# xdoftof_revA.net
KiCad netlist of a schematic drawn in EAGLE
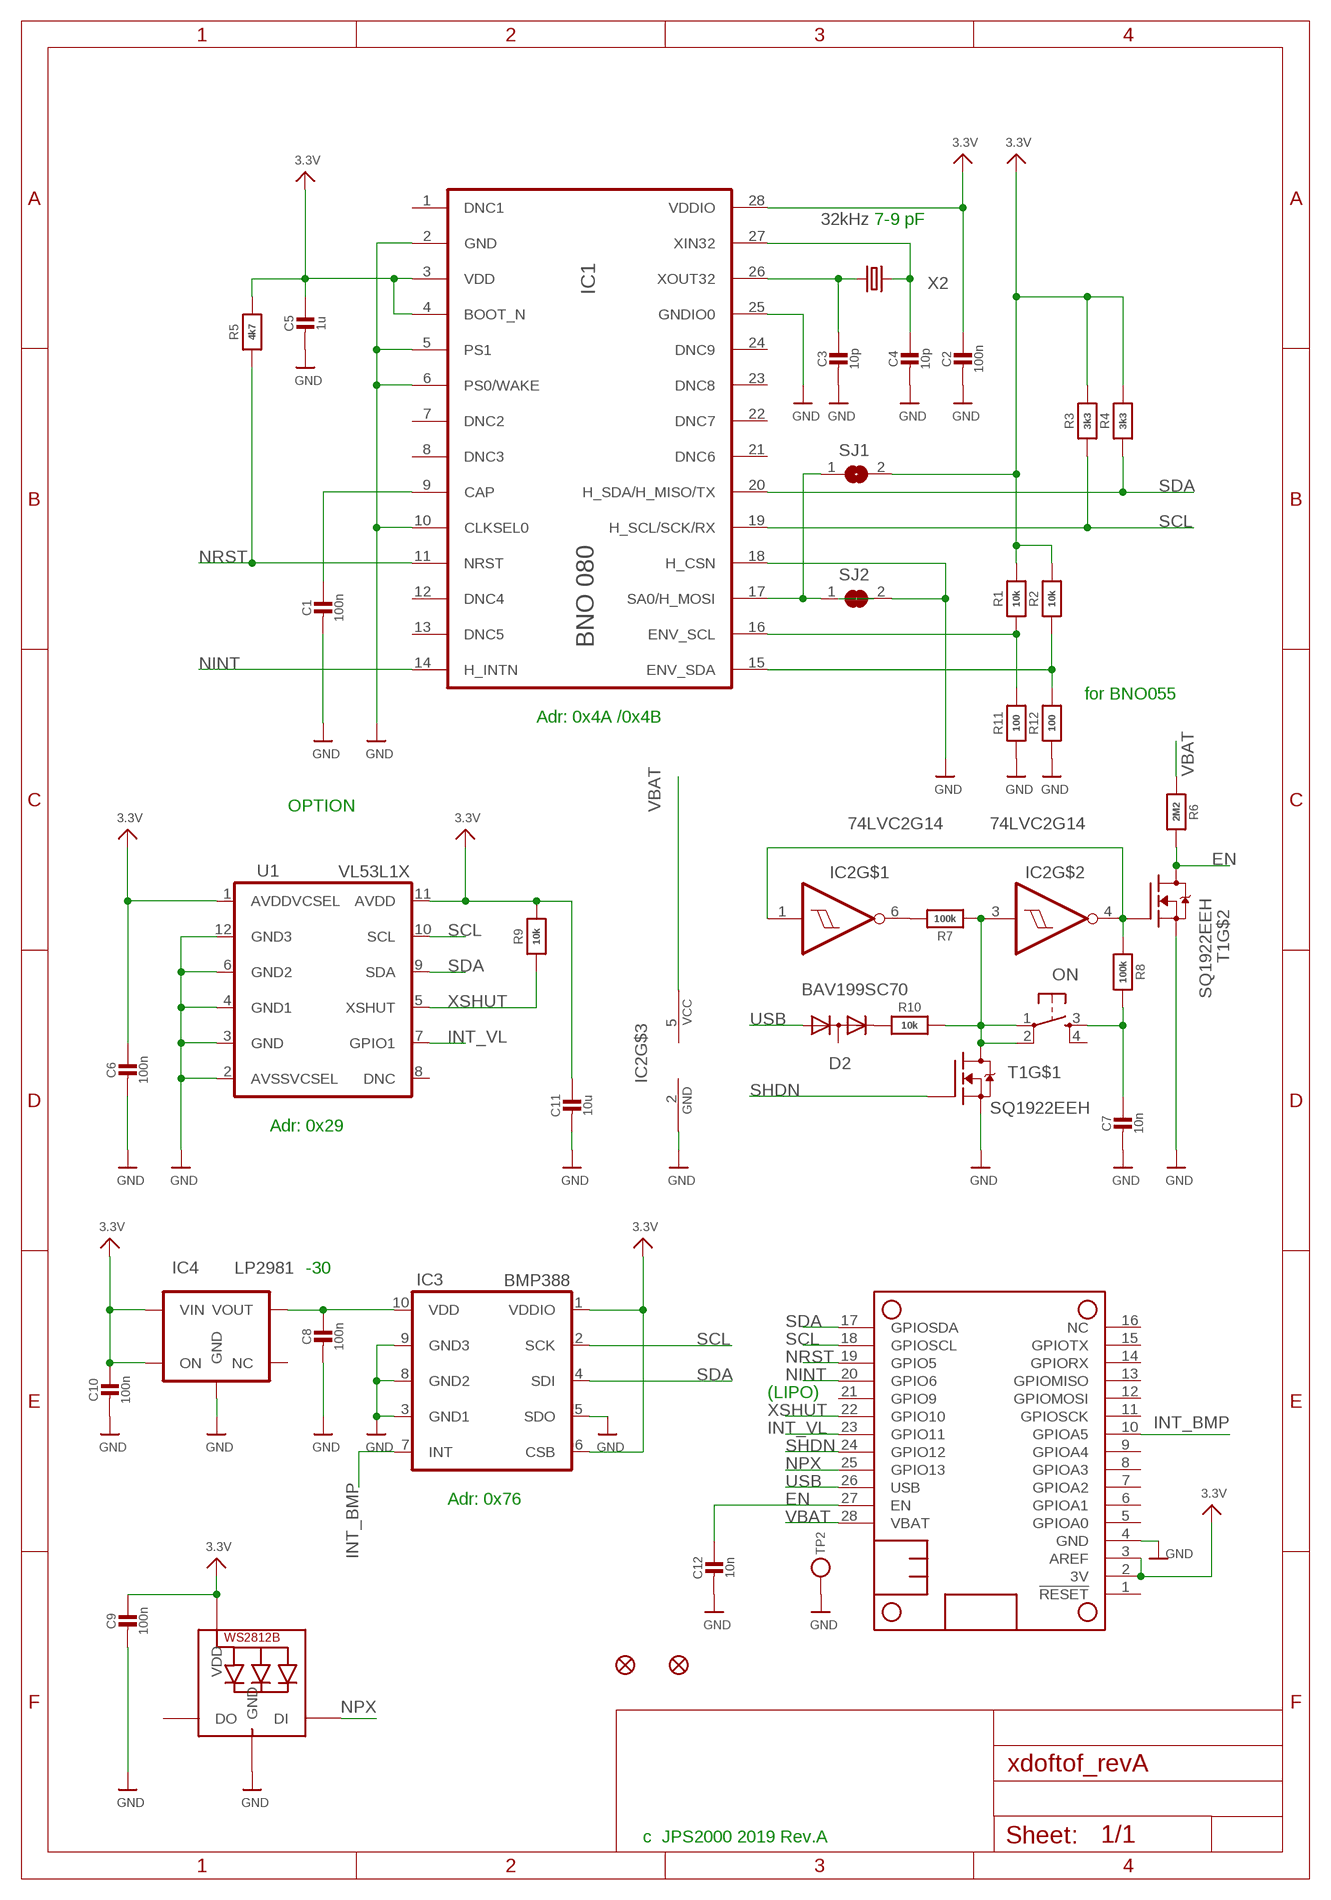
[diagram p0: schematic, sheet 1]

(export (version "E")
  (design (tool "Eeschema 10.0.6"))
  (components
    (comp (ref "C1")
      (value "100n")
      (footprint "eagle-import:0603-NO")
      (libsource (lib "eagle-import") (part "CAP_CERAMIC0603_NO"))
    )
    (comp (ref "C2")
      (value "100n")
      (footprint "eagle-import:0603-NO")
      (libsource (lib "eagle-import") (part "CAP_CERAMIC0603_NO"))
    )
    (comp (ref "C3")
      (value "10p")
      (footprint "eagle-import:0603-NO")
      (libsource (lib "eagle-import") (part "CAP_CERAMIC0603_NO"))
    )
    (comp (ref "C4")
      (value "10p")
      (footprint "eagle-import:0603-NO")
      (libsource (lib "eagle-import") (part "CAP_CERAMIC0603_NO"))
    )
    (comp (ref "C5")
      (value "1u")
      (footprint "eagle-import:0603-NO")
      (libsource (lib "eagle-import") (part "CAP_CERAMIC0603_NO"))
    )
    (comp (ref "C6")
      (value "100n")
      (footprint "eagle-import:0603-NO")
      (libsource (lib "eagle-import") (part "CAP_CERAMIC0603_NO"))
    )
    (comp (ref "C7")
      (value "10n")
      (footprint "eagle-import:0603-NO")
      (libsource (lib "eagle-import") (part "CAP_CERAMIC0603_NO"))
    )
    (comp (ref "C8")
      (value "100n")
      (footprint "eagle-import:0603-NO")
      (libsource (lib "eagle-import") (part "CAP_CERAMIC0603_NO"))
    )
    (comp (ref "C9")
      (value "100n")
      (footprint "eagle-import:0603-NO")
      (libsource (lib "eagle-import") (part "CAP_CERAMIC0603_NO"))
    )
    (comp (ref "C10")
      (value "100n")
      (footprint "eagle-import:0603-NO")
      (libsource (lib "eagle-import") (part "CAP_CERAMIC0603_NO"))
    )
    (comp (ref "C11")
      (value "10u")
      (footprint "eagle-import:0603-NO")
      (libsource (lib "eagle-import") (part "CAP_CERAMIC0603_NO"))
    )
    (comp (ref "C12")
      (value "10n")
      (footprint "eagle-import:0603-NO")
      (libsource (lib "eagle-import") (part "CAP_CERAMIC0603_NO"))
    )
    (comp (ref "D2")
      (value "BAV199SC70")
      (footprint "eagle-import:SC70")
      (libsource (lib "eagle-import") (part "BAV199SC70"))
    )
    (comp (ref "FID1")
      (value "FIDUCIAL\"\"")
      (footprint "eagle-import:FIDUCIAL_1MM")
      (libsource (lib "eagle-import") (part "FIDUCIAL{dblquote}{dblquote}"))
    )
    (comp (ref "FID2")
      (value "FIDUCIAL\"\"")
      (footprint "eagle-import:FIDUCIAL_1MM")
      (libsource (lib "eagle-import") (part "FIDUCIAL{dblquote}{dblquote}"))
    )
    (comp (ref "IC1")
      (value "BNO080")
      (footprint "eagle-import:LGA28")
      (libsource (lib "eagle-import") (part "BNO080"))
    )
    (comp (ref "IC2")
      (value "74LVC2G14")
      (footprint "eagle-import:SC70-6")
      (libsource (lib "eagle-import") (part "74LVC2G14"))
    )
    (comp (ref "IC3")
      (value "BMP388")
      (footprint "eagle-import:LGA10")
      (libsource (lib "eagle-import") (part "BMP388"))
    )
    (comp (ref "IC4")
      (value "LP2981")
      (footprint "eagle-import:SOT23-5_NEW")
      (libsource (lib "eagle-import") (part "LP2981"))
    )
    (comp (ref "LED1")
      (value "WS2812B3535")
      (footprint "eagle-import:LED3535")
      (libsource (lib "eagle-import") (part "WS2812B3535"))
    )
    (comp (ref "MS1")
      (value "FEATHERWING_NOHOLES")
      (footprint "eagle-import:FEATHERWING_NOHOLES")
      (libsource (lib "eagle-import") (part "FEATHERWING_NOHOLES"))
    )
    (comp (ref "ON")
      (value "ON/OFF")
      (footprint "eagle-import:TACTSWSKQGABE010")
      (libsource (lib "eagle-import") (part "TACTSW_SMD"))
    )
    (comp (ref "R1")
      (value "10k")
      (footprint "eagle-import:_0603MP")
      (libsource (lib "eagle-import") (part "RESISTOR_0603MP"))
    )
    (comp (ref "R2")
      (value "10k")
      (footprint "eagle-import:_0603MP")
      (libsource (lib "eagle-import") (part "RESISTOR_0603MP"))
    )
    (comp (ref "R3")
      (value "3k3")
      (footprint "eagle-import:_0603MP")
      (libsource (lib "eagle-import") (part "RESISTOR_0603MP"))
    )
    (comp (ref "R4")
      (value "3k3")
      (footprint "eagle-import:_0603MP")
      (libsource (lib "eagle-import") (part "RESISTOR_0603MP"))
    )
    (comp (ref "R5")
      (value "4k7")
      (footprint "eagle-import:_0603MP")
      (libsource (lib "eagle-import") (part "RESISTOR_0603MP"))
    )
    (comp (ref "R6")
      (value "2M2")
      (footprint "eagle-import:_0603MP")
      (libsource (lib "eagle-import") (part "RESISTOR_0603MP"))
    )
    (comp (ref "R7")
      (value "100k")
      (footprint "eagle-import:_0603MP")
      (libsource (lib "eagle-import") (part "RESISTOR_0603MP"))
    )
    (comp (ref "R8")
      (value "100k")
      (footprint "eagle-import:_0603MP")
      (libsource (lib "eagle-import") (part "RESISTOR_0603MP"))
    )
    (comp (ref "R9")
      (value "10k")
      (footprint "eagle-import:_0603MP")
      (libsource (lib "eagle-import") (part "RESISTOR_0603MP"))
    )
    (comp (ref "R10")
      (value "10k")
      (footprint "eagle-import:_0603MP")
      (libsource (lib "eagle-import") (part "RESISTOR_0603MP"))
    )
    (comp (ref "R11")
      (value "100")
      (footprint "eagle-import:_0603MP")
      (libsource (lib "eagle-import") (part "RESISTOR_0603MP"))
    )
    (comp (ref "R12")
      (value "100")
      (footprint "eagle-import:_0603MP")
      (libsource (lib "eagle-import") (part "RESISTOR_0603MP"))
    )
    (comp (ref "SJ1")
      (value "SOLDERJUMPERREFLOW_NOPASTE")
      (footprint "eagle-import:SOLDERJUMPER_REFLOW_NOPASTE")
      (libsource (lib "eagle-import") (part "SOLDERJUMPERREFLOW_NOPASTE"))
    )
    (comp (ref "SJ2")
      (value "SOLDERJUMPERCLOSED")
      (footprint "eagle-import:SOLDERJUMPER_CLOSEDWIRE")
      (libsource (lib "eagle-import") (part "SOLDERJUMPERCLOSED"))
    )
    (comp (ref "T1")
      (value "SQ1922EEH")
      (footprint "eagle-import:SC70-6")
      (libsource (lib "eagle-import") (part "DUAL_NMOS"))
    )
    (comp (ref "TP2")
      (value "TESTPOINTROUND1MM")
      (footprint "eagle-import:TESTPOINT_ROUND_1MM")
      (libsource (lib "eagle-import") (part "TESTPOINTROUND1MM"))
    )
    (comp (ref "U1")
      (value "VL53L1X")
      (footprint "eagle-import:VL53L1X")
      (libsource (lib "eagle-import") (part "VL53L1X"))
    )
    (comp (ref "X2")
      (value "32kHz")
      (footprint "eagle-import:XTAL_SMD1")
      (libsource (lib "eagle-import") (part "XTAL_SMD"))
    )
  )
  (nets
    (net (code "1") (name "/EN") (class "Default")
      (node (ref "C12") (pin "1") (pinfunction "1_1") (pintype "passive"))
      (node (ref "MS1") (pin "27") (pinfunction "EN_27") (pintype "passive"))
      (node (ref "R6") (pin "2") (pinfunction "2_2") (pintype "passive"))
      (node (ref "T1") (pin "3") (pinfunction "D_3") (pintype "passive"))
    )
    (net (code "2") (name "/INT_BMP") (class "Default")
      (node (ref "IC3") (pin "7") (pinfunction "INT_7") (pintype "output"))
      (node (ref "MS1") (pin "10") (pinfunction "GPIOA5_10") (pintype "bidirectional"))
    )
    (net (code "3") (name "/INT_VL") (class "Default")
      (node (ref "MS1") (pin "23") (pinfunction "GPIO11_23") (pintype "bidirectional"))
      (node (ref "U1") (pin "7") (pinfunction "GPIO1_7") (pintype "bidirectional"))
    )
    (net (code "4") (name "/NINT") (class "Default")
      (node (ref "IC1") (pin "14") (pinfunction "H_INTN_14") (pintype "output"))
      (node (ref "MS1") (pin "20") (pinfunction "GPIO6_20") (pintype "bidirectional"))
    )
    (net (code "5") (name "/NPX") (class "Default")
      (node (ref "LED1") (pin "1") (pinfunction "DI_1") (pintype "input"))
      (node (ref "MS1") (pin "25") (pinfunction "GPIO13_25") (pintype "bidirectional"))
    )
    (net (code "6") (name "/NRST") (class "Default")
      (node (ref "IC1") (pin "11") (pinfunction "NRST_11") (pintype "input"))
      (node (ref "MS1") (pin "19") (pinfunction "GPIO5_19") (pintype "bidirectional"))
      (node (ref "R5") (pin "1") (pinfunction "1_1") (pintype "passive"))
    )
    (net (code "7") (name "/SCL") (class "Default")
      (node (ref "IC1") (pin "19") (pinfunction "H_SCL/SCK/RX_19") (pintype "input"))
      (node (ref "IC3") (pin "2") (pinfunction "SCK_2") (pintype "input"))
      (node (ref "MS1") (pin "18") (pinfunction "GPIOSCL_18") (pintype "bidirectional"))
      (node (ref "R3") (pin "1") (pinfunction "1_1") (pintype "passive"))
      (node (ref "U1") (pin "10") (pinfunction "SCL_10") (pintype "input"))
    )
    (net (code "8") (name "/SDA") (class "Default")
      (node (ref "IC1") (pin "20") (pinfunction "H_SDA/H_MISO/TX_20") (pintype "bidirectional"))
      (node (ref "IC3") (pin "4") (pinfunction "SDI_4") (pintype "input"))
      (node (ref "MS1") (pin "17") (pinfunction "GPIOSDA_17") (pintype "bidirectional"))
      (node (ref "R4") (pin "1") (pinfunction "1_1") (pintype "passive"))
      (node (ref "U1") (pin "9") (pinfunction "SDA_9") (pintype "input"))
    )
    (net (code "9") (name "/SHDN") (class "Default")
      (node (ref "MS1") (pin "24") (pinfunction "GPIO12_24") (pintype "bidirectional"))
      (node (ref "T1") (pin "2") (pinfunction "G_2") (pintype "passive"))
    )
    (net (code "10") (name "/USB") (class "Default")
      (node (ref "D2") (pin "1") (pinfunction "A_1") (pintype "passive"))
      (node (ref "MS1") (pin "26") (pinfunction "USB_26") (pintype "power_in"))
    )
    (net (code "11") (name "/VBAT") (class "Default")
      (node (ref "IC2") (pin "5") (pinfunction "VCC_5") (pintype "power_in"))
      (node (ref "MS1") (pin "28") (pinfunction "VBAT_28") (pintype "power_in"))
      (node (ref "R6") (pin "1") (pinfunction "1_1") (pintype "passive"))
    )
    (net (code "12") (name "/XSHUT") (class "Default")
      (node (ref "MS1") (pin "22") (pinfunction "GPIO10_22") (pintype "bidirectional"))
      (node (ref "R9") (pin "1") (pinfunction "1_1") (pintype "passive"))
      (node (ref "U1") (pin "5") (pinfunction "XSHUT_5") (pintype "output"))
    )
    (net (code "13") (name "3.3V") (class "Default")
      (node (ref "C10") (pin "1") (pinfunction "1_1") (pintype "passive"))
      (node (ref "C11") (pin "1") (pinfunction "1_1") (pintype "passive"))
      (node (ref "C2") (pin "1") (pinfunction "1_1") (pintype "passive"))
      (node (ref "C5") (pin "1") (pinfunction "1_1") (pintype "passive"))
      (node (ref "C6") (pin "1") (pinfunction "1_1") (pintype "passive"))
      (node (ref "C9") (pin "1") (pinfunction "1_1") (pintype "passive"))
      (node (ref "IC1") (pin "28") (pinfunction "VDDIO_28") (pintype "power_in"))
      (node (ref "IC1") (pin "3") (pinfunction "VDD_3") (pintype "power_in"))
      (node (ref "IC1") (pin "4") (pinfunction "BOOT_N_4") (pintype "input"))
      (node (ref "IC3") (pin "1") (pinfunction "VDDIO_1") (pintype "power_in"))
      (node (ref "IC3") (pin "6") (pinfunction "CSB_6") (pintype "bidirectional"))
      (node (ref "IC4") (pin "P$1") (pinfunction "VIN_P$1") (pintype "power_in"))
      (node (ref "IC4") (pin "P$3") (pinfunction "ON_P$3") (pintype "input"))
      (node (ref "LED1") (pin "2") (pinfunction "VDD_2") (pintype "power_in"))
      (node (ref "MS1") (pin "2") (pinfunction "3V_2") (pintype "power_in"))
      (node (ref "MS1") (pin "3") (pinfunction "AREF_3") (pintype "passive"))
      (node (ref "R1") (pin "2") (pinfunction "2_2") (pintype "passive"))
      (node (ref "R2") (pin "2") (pinfunction "2_2") (pintype "passive"))
      (node (ref "R3") (pin "2") (pinfunction "2_2") (pintype "passive"))
      (node (ref "R4") (pin "2") (pinfunction "2_2") (pintype "passive"))
      (node (ref "R5") (pin "2") (pinfunction "2_2") (pintype "passive"))
      (node (ref "R9") (pin "2") (pinfunction "2_2") (pintype "passive"))
      (node (ref "SJ1") (pin "2") (pinfunction "2_2") (pintype "passive"))
      (node (ref "U1") (pin "1") (pinfunction "AVDDVCSEL_1") (pintype "power_in"))
      (node (ref "U1") (pin "11") (pinfunction "AVDD_11") (pintype "power_in"))
    )
    (net (code "14") (name "GND") (class "Default")
      (node (ref "C1") (pin "2") (pinfunction "2_2") (pintype "passive"))
      (node (ref "C10") (pin "2") (pinfunction "2_2") (pintype "passive"))
      (node (ref "C11") (pin "2") (pinfunction "2_2") (pintype "passive"))
      (node (ref "C12") (pin "2") (pinfunction "2_2") (pintype "passive"))
      (node (ref "C2") (pin "2") (pinfunction "2_2") (pintype "passive"))
      (node (ref "C3") (pin "2") (pinfunction "2_2") (pintype "passive"))
      (node (ref "C4") (pin "2") (pinfunction "2_2") (pintype "passive"))
      (node (ref "C5") (pin "2") (pinfunction "2_2") (pintype "passive"))
      (node (ref "C6") (pin "2") (pinfunction "2_2") (pintype "passive"))
      (node (ref "C7") (pin "2") (pinfunction "2_2") (pintype "passive"))
      (node (ref "C8") (pin "2") (pinfunction "2_2") (pintype "passive"))
      (node (ref "C9") (pin "2") (pinfunction "2_2") (pintype "passive"))
      (node (ref "IC1") (pin "10") (pinfunction "CLKSEL0_10") (pintype "power_in"))
      (node (ref "IC1") (pin "18") (pinfunction "H_CSN_18") (pintype "input"))
      (node (ref "IC1") (pin "2") (pinfunction "GND_2") (pintype "power_in"))
      (node (ref "IC1") (pin "25") (pinfunction "GNDIO0_25") (pintype "power_in"))
      (node (ref "IC1") (pin "5") (pinfunction "PS1_5") (pintype "input"))
      (node (ref "IC1") (pin "6") (pinfunction "PS0/WAKE_6") (pintype "input"))
      (node (ref "IC2") (pin "2") (pinfunction "GND_2") (pintype "power_in"))
      (node (ref "IC3") (pin "3") (pinfunction "GND1_3") (pintype "power_in"))
      (node (ref "IC3") (pin "5") (pinfunction "SDO_5") (pintype "output"))
      (node (ref "IC3") (pin "8") (pinfunction "GND2_8") (pintype "power_in"))
      (node (ref "IC3") (pin "9") (pinfunction "GND3_9") (pintype "power_in"))
      (node (ref "IC4") (pin "P$2") (pinfunction "GND_P$2") (pintype "power_in"))
      (node (ref "LED1") (pin "4") (pinfunction "GND_4") (pintype "power_in"))
      (node (ref "MS1") (pin "4") (pinfunction "GND_4") (pintype "power_in"))
      (node (ref "R11") (pin "1") (pinfunction "1_1") (pintype "passive"))
      (node (ref "R12") (pin "1") (pinfunction "1_1") (pintype "passive"))
      (node (ref "SJ2") (pin "2") (pinfunction "2_2") (pintype "passive"))
      (node (ref "T1") (pin "1") (pinfunction "S_1") (pintype "passive"))
      (node (ref "T1") (pin "4") (pinfunction "S_4") (pintype "passive"))
      (node (ref "TP2") (pin "P$1") (pinfunction "P$1_P$1") (pintype "bidirectional"))
      (node (ref "U1") (pin "12") (pinfunction "GND3_12") (pintype "power_in"))
      (node (ref "U1") (pin "2") (pinfunction "AVSSVCSEL_2") (pintype "power_in"))
      (node (ref "U1") (pin "3") (pinfunction "GND_3") (pintype "power_in"))
      (node (ref "U1") (pin "4") (pinfunction "GND1_4") (pintype "power_in"))
      (node (ref "U1") (pin "6") (pinfunction "GND2_6") (pintype "power_in"))
    )
    (net (code "15") (name "Net-(C7-Pad1)") (class "Default")
      (node (ref "C7") (pin "1") (pinfunction "1_1") (pintype "passive"))
      (node (ref "ON") (pin "3") (pinfunction "3_3") (pintype "bidirectional"))
      (node (ref "R8") (pin "2") (pinfunction "2_2") (pintype "passive"))
    )
    (net (code "16") (name "Net-(D2-C)") (class "Default")
      (node (ref "D2") (pin "2") (pinfunction "C_2") (pintype "passive"))
      (node (ref "R10") (pin "1") (pinfunction "1_1") (pintype "passive"))
    )
    (net (code "17") (name "Net-(IC1-CAP)") (class "Default")
      (node (ref "C1") (pin "1") (pinfunction "1_1") (pintype "passive"))
      (node (ref "IC1") (pin "9") (pinfunction "CAP_9") (pintype "input"))
    )
    (net (code "18") (name "Net-(IC1-ENV_SCL)") (class "Default")
      (node (ref "IC1") (pin "16") (pinfunction "ENV_SCL_16") (pintype "power_in"))
      (node (ref "R1") (pin "1") (pinfunction "1_1") (pintype "passive"))
      (node (ref "R11") (pin "2") (pinfunction "2_2") (pintype "passive"))
    )
    (net (code "19") (name "Net-(IC1-ENV_SDA)") (class "Default")
      (node (ref "IC1") (pin "15") (pinfunction "ENV_SDA_15") (pintype "power_in"))
      (node (ref "R12") (pin "2") (pinfunction "2_2") (pintype "passive"))
      (node (ref "R2") (pin "1") (pinfunction "1_1") (pintype "passive"))
    )
    (net (code "20") (name "Net-(IC1-SA0{slash}H_MOSI)") (class "Default")
      (node (ref "IC1") (pin "17") (pinfunction "SA0/H_MOSI_17") (pintype "input"))
      (node (ref "SJ1") (pin "1") (pinfunction "1_1") (pintype "passive"))
      (node (ref "SJ2") (pin "1") (pinfunction "1_1") (pintype "passive"))
    )
    (net (code "21") (name "Net-(IC1-XIN32)") (class "Default")
      (node (ref "C4") (pin "1") (pinfunction "1_1") (pintype "passive"))
      (node (ref "IC1") (pin "27") (pinfunction "XIN32_27") (pintype "input"))
      (node (ref "X2") (pin "P$2") (pinfunction "2_P$2") (pintype "passive"))
    )
    (net (code "22") (name "Net-(IC1-XOUT32)") (class "Default")
      (node (ref "C3") (pin "1") (pinfunction "1_1") (pintype "passive"))
      (node (ref "IC1") (pin "26") (pinfunction "XOUT32_26") (pintype "output"))
      (node (ref "X2") (pin "P$1") (pinfunction "1_P$1") (pintype "passive"))
    )
    (net (code "23") (name "Net-(IC2A-I)") (class "Default")
      (node (ref "IC2") (pin "1") (pinfunction "I_1") (pintype "input"))
      (node (ref "IC2") (pin "4") (pinfunction "O_4") (pintype "output"))
      (node (ref "R8") (pin "1") (pinfunction "1_1") (pintype "passive"))
      (node (ref "T1") (pin "5") (pinfunction "G_5") (pintype "passive"))
    )
    (net (code "24") (name "Net-(IC2A-O)") (class "Default")
      (node (ref "IC2") (pin "6") (pinfunction "O_6") (pintype "output"))
      (node (ref "R7") (pin "2") (pinfunction "2_2") (pintype "passive"))
    )
    (net (code "25") (name "Net-(IC2B-I)") (class "Default")
      (node (ref "IC2") (pin "3") (pinfunction "I_3") (pintype "input"))
      (node (ref "ON") (pin "1") (pinfunction "1_1") (pintype "bidirectional"))
      (node (ref "ON") (pin "2") (pinfunction "2_2") (pintype "bidirectional"))
      (node (ref "R10") (pin "2") (pinfunction "2_2") (pintype "passive"))
      (node (ref "R7") (pin "1") (pinfunction "1_1") (pintype "passive"))
      (node (ref "T1") (pin "6") (pinfunction "D_6") (pintype "passive"))
    )
    (net (code "26") (name "Net-(IC3-VDD)") (class "Default")
      (node (ref "C8") (pin "1") (pinfunction "1_1") (pintype "passive"))
      (node (ref "IC3") (pin "10") (pinfunction "VDD_10") (pintype "power_in"))
      (node (ref "IC4") (pin "P$5") (pinfunction "VOUT_P$5") (pintype "power_in"))
    )
    (net (code "27") (name "unconnected-(D2-AC-Pad3)") (class "Default")
      (node (ref "D2") (pin "3") (pinfunction "AC_3") (pintype "passive"))
    )
    (net (code "28") (name "unconnected-(IC1-DNC1-Pad1)") (class "Default")
      (node (ref "IC1") (pin "1") (pinfunction "DNC1_1") (pintype "no_connect"))
    )
    (net (code "29") (name "unconnected-(IC1-DNC2-Pad7)") (class "Default")
      (node (ref "IC1") (pin "7") (pinfunction "DNC2_7") (pintype "no_connect"))
    )
    (net (code "30") (name "unconnected-(IC1-DNC3-Pad8)") (class "Default")
      (node (ref "IC1") (pin "8") (pinfunction "DNC3_8") (pintype "no_connect"))
    )
    (net (code "31") (name "unconnected-(IC1-DNC4-Pad12)") (class "Default")
      (node (ref "IC1") (pin "12") (pinfunction "DNC4_12") (pintype "no_connect"))
    )
    (net (code "32") (name "unconnected-(IC1-DNC5-Pad13)") (class "Default")
      (node (ref "IC1") (pin "13") (pinfunction "DNC5_13") (pintype "no_connect"))
    )
    (net (code "33") (name "unconnected-(IC1-DNC6-Pad21)") (class "Default")
      (node (ref "IC1") (pin "21") (pinfunction "DNC6_21") (pintype "no_connect"))
    )
    (net (code "34") (name "unconnected-(IC1-DNC7-Pad22)") (class "Default")
      (node (ref "IC1") (pin "22") (pinfunction "DNC7_22") (pintype "no_connect"))
    )
    (net (code "35") (name "unconnected-(IC1-DNC8-Pad23)") (class "Default")
      (node (ref "IC1") (pin "23") (pinfunction "DNC8_23") (pintype "no_connect"))
    )
    (net (code "36") (name "unconnected-(IC1-DNC9-Pad24)") (class "Default")
      (node (ref "IC1") (pin "24") (pinfunction "DNC9_24") (pintype "no_connect"))
    )
    (net (code "37") (name "unconnected-(IC4-NC-PadP$4)") (class "Default")
      (node (ref "IC4") (pin "P$4") (pinfunction "NC_P$4") (pintype "no_connect"))
    )
    (net (code "38") (name "unconnected-(LED1-DO-Pad3)") (class "Default")
      (node (ref "LED1") (pin "3") (pinfunction "DO_3") (pintype "output"))
    )
    (net (code "39") (name "unconnected-(MS1-GPIO9-Pad21)") (class "Default")
      (node (ref "MS1") (pin "21") (pinfunction "GPIO9_21") (pintype "bidirectional"))
    )
    (net (code "40") (name "unconnected-(MS1-GPIOA0-Pad5)") (class "Default")
      (node (ref "MS1") (pin "5") (pinfunction "GPIOA0_5") (pintype "bidirectional"))
    )
    (net (code "41") (name "unconnected-(MS1-GPIOA1-Pad6)") (class "Default")
      (node (ref "MS1") (pin "6") (pinfunction "GPIOA1_6") (pintype "bidirectional"))
    )
    (net (code "42") (name "unconnected-(MS1-GPIOA2-Pad7)") (class "Default")
      (node (ref "MS1") (pin "7") (pinfunction "GPIOA2_7") (pintype "bidirectional"))
    )
    (net (code "43") (name "unconnected-(MS1-GPIOA3-Pad8)") (class "Default")
      (node (ref "MS1") (pin "8") (pinfunction "GPIOA3_8") (pintype "bidirectional"))
    )
    (net (code "44") (name "unconnected-(MS1-GPIOA4-Pad9)") (class "Default")
      (node (ref "MS1") (pin "9") (pinfunction "GPIOA4_9") (pintype "bidirectional"))
    )
    (net (code "45") (name "unconnected-(MS1-GPIOMISO-Pad13)") (class "Default")
      (node (ref "MS1") (pin "13") (pinfunction "GPIOMISO_13") (pintype "bidirectional"))
    )
    (net (code "46") (name "unconnected-(MS1-GPIOMOSI-Pad12)") (class "Default")
      (node (ref "MS1") (pin "12") (pinfunction "GPIOMOSI_12") (pintype "bidirectional"))
    )
    (net (code "47") (name "unconnected-(MS1-GPIORX-Pad14)") (class "Default")
      (node (ref "MS1") (pin "14") (pinfunction "GPIORX_14") (pintype "bidirectional"))
    )
    (net (code "48") (name "unconnected-(MS1-GPIOSCK-Pad11)") (class "Default")
      (node (ref "MS1") (pin "11") (pinfunction "GPIOSCK_11") (pintype "bidirectional"))
    )
    (net (code "49") (name "unconnected-(MS1-GPIOTX-Pad15)") (class "Default")
      (node (ref "MS1") (pin "15") (pinfunction "GPIOTX_15") (pintype "bidirectional"))
    )
    (net (code "50") (name "unconnected-(MS1-NC-Pad16)") (class "Default")
      (node (ref "MS1") (pin "16") (pinfunction "NC_16") (pintype "passive"))
    )
    (net (code "51") (name "unconnected-(MS1-~{RESET}-Pad1)") (class "Default")
      (node (ref "MS1") (pin "1") (pinfunction "~{RESET}_1") (pintype "input"))
    )
    (net (code "52") (name "unconnected-(ON-Pad4)") (class "Default")
      (node (ref "ON") (pin "4") (pinfunction "4_4") (pintype "bidirectional"))
    )
    (net (code "53") (name "unconnected-(U1-DNC-Pad8)") (class "Default")
      (node (ref "U1") (pin "8") (pinfunction "DNC_8") (pintype "no_connect"))
    )
  )
)
